# IWRL6432AOP.net
KiCad netlist of a schematic drawn in Altium Designer
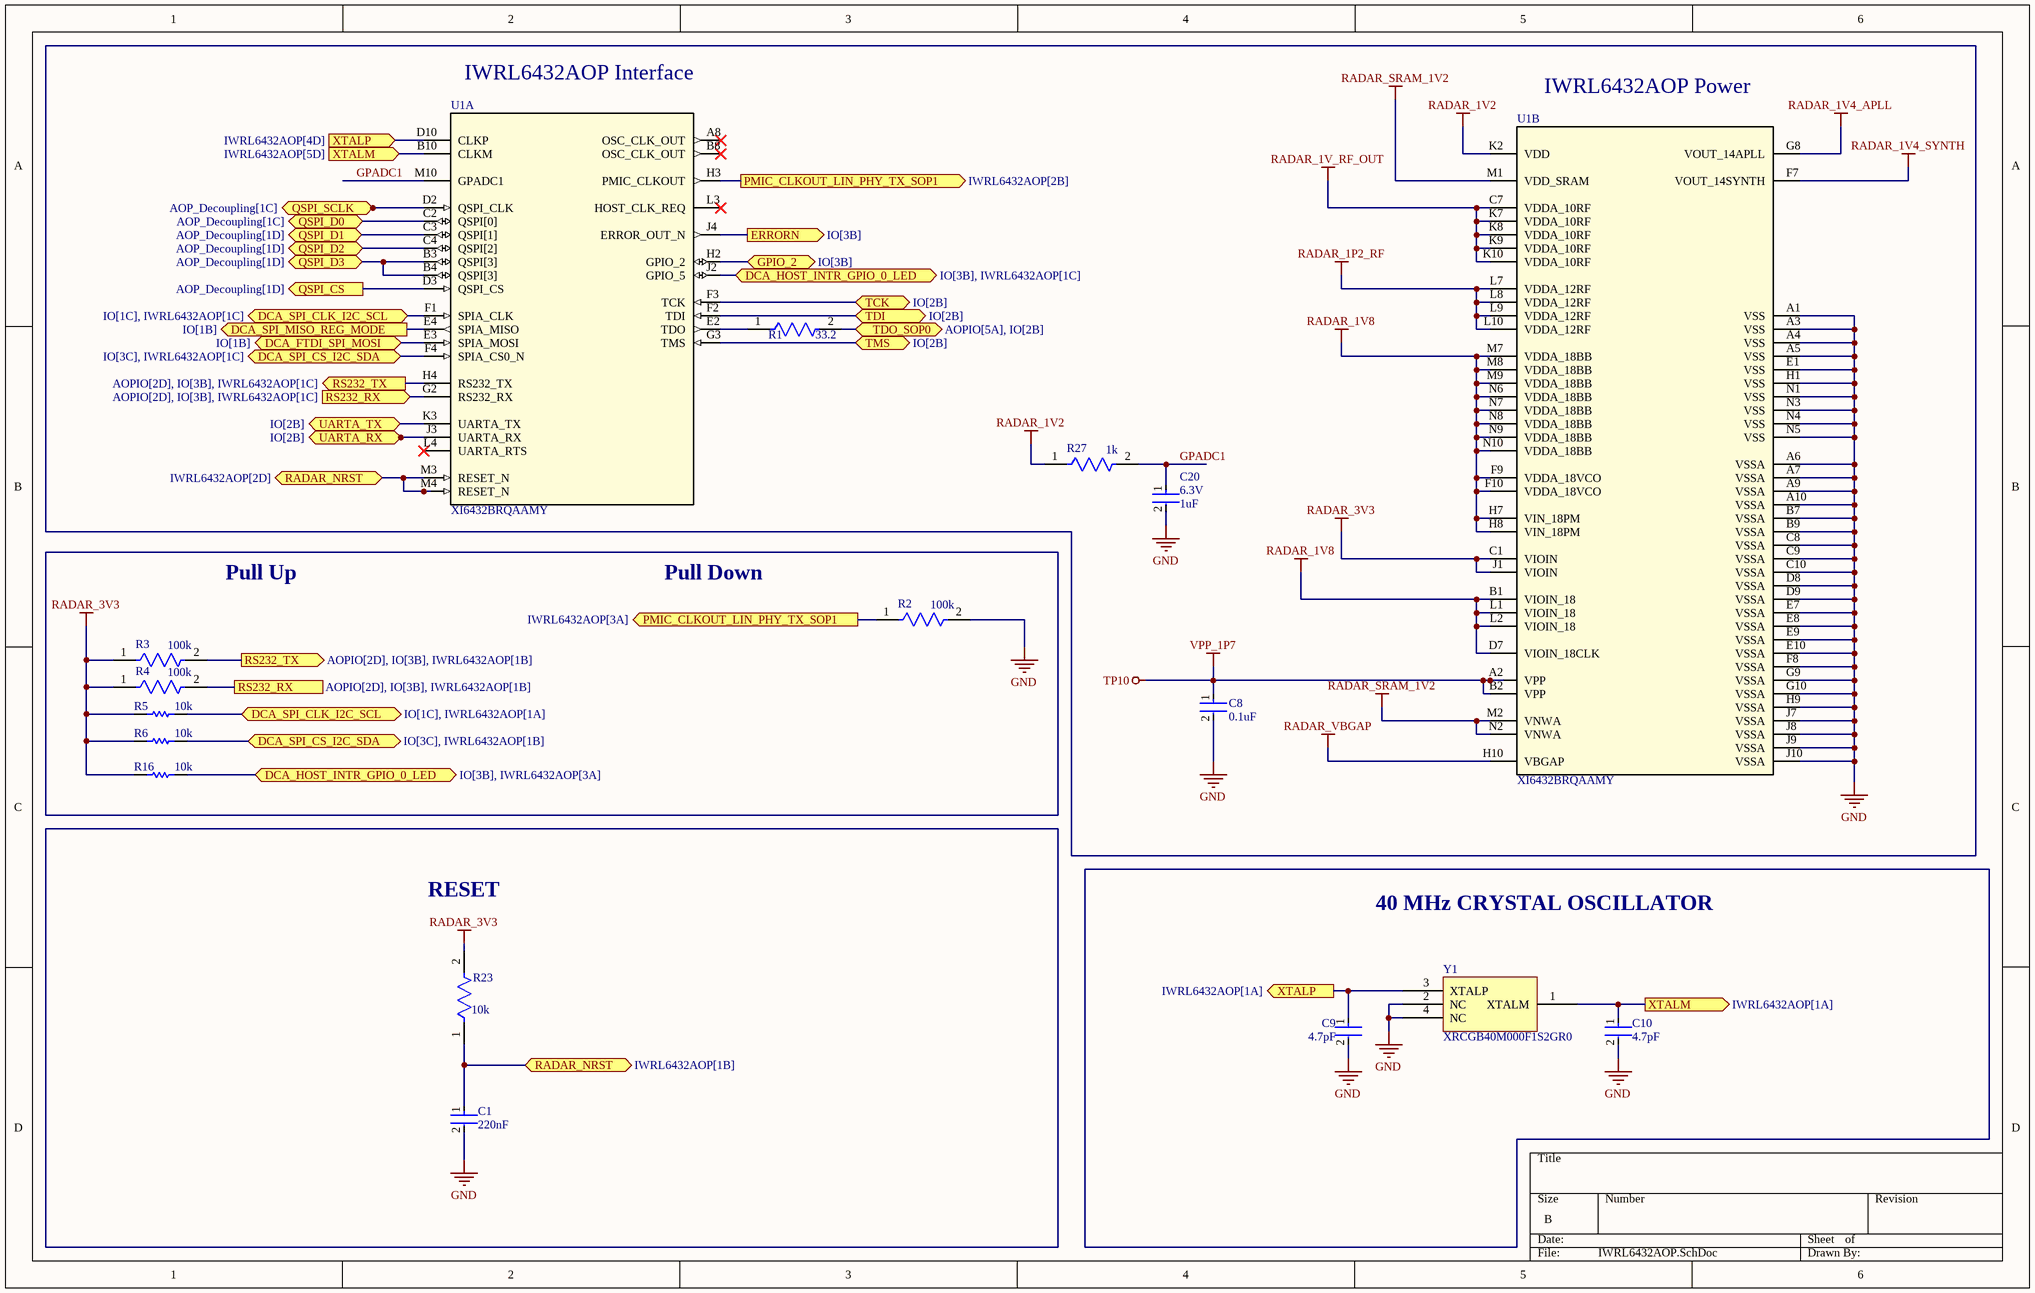
[diagram p0: IWRL6432AOP.SchDoc]

(export (version "E")
  (design (tool "Eeschema 10.0.6"))
  (components
    (comp (ref "C1")
      (value "CL05B224KO5NNNC")
      (footprint "FP-CL549-IPC_C")
      (description "Cap Ceramic 220nF 16V X7R ±10% SMD 0402 +125°C Paper T/R")
      (fields (field (name "CAPACITANCE") "220nF") (field (name "TOLERANCE") "10%"))
      (libsource (lib "Altium Content Vault") (part "b4654b650e69147ec39a6b967a45e02"))
    )
    (comp (ref "C8")
      (value "0.1uF")
      (footprint "FP-C0402-BB-MFG")
      (description "CAP CER 0.1UF 10V X7R 0402")
      (fields
        (field (name "OCTOPART") "https://octopart.com/c0402c104k8ractu-kemet-106349")
        (field (name "MANUFACTURER PART NUMBER") "C0402C104K8RACTU")
      )
      (libsource (lib "Altium Content Vault") (part "b4654b650e69147ec39a6b967a45e02"))
    )
    (comp (ref "C9")
      (value "GJM1555C1H4R7BB01D")
      (footprint "FP-GJM155-0_05-IPC_C")
      (description "Multi-Layer Ceramic Capacitor 4.7pF C0G  ±0.1pF 0402 Paper T/R")
      (fields (field (name "CAPACITANCE") "4.7pF"))
      (libsource (lib "Altium Content Vault") (part "02cd4be3c70576c341d710602a673aa"))
    )
    (comp (ref "C10")
      (value "GJM1555C1H4R7BB01D")
      (footprint "FP-GJM155-0_05-IPC_C")
      (description "Multi-Layer Ceramic Capacitor 4.7pF C0G  ±0.1pF 0402 Paper T/R")
      (fields (field (name "CAPACITANCE") "4.7pF"))
      (libsource (lib "Altium Content Vault") (part "02cd4be3c70576c341d710602a673aa"))
    )
    (comp (ref "C20")
      (value "GRM155C80J105KA12D")
      (footprint "FP-GRM155-0_05-IPC_C")
      (description "Chip Multilayer Ceramic Capacitors for General Purpose, 0402, 1.0uF, X6S, 22%, 10%, 6.3V")
      (fields
        (field (name "CAPACITANCE") "1uF")
        (field (name "TOLERANCE") "10%")
        (field (name "VOLTAGE RATING (DC)") "6.3V")
      )
      (libsource (lib "Altium Content Vault") (part "02cd4be3c70576c341d710602a673aa"))
    )
    (comp (ref "R1")
      (value "RT0402FRE0733R2L")
      (footprint "FP-RT0402-0_35-MFG")
      (fields (field (name "TOLERANCE") "1%") (field (name "RESISTANCE") "33.2"))
      (libsource (lib "Altium Content Vault") (part "1029c3af85768c4190bb7ad29bc67b5"))
    )
    (comp (ref "R2")
      (value "CRCW0402100KFKEDC")
      (footprint "FP-CRCW0402-C-e3-MFG")
      (description "RES 100K OHM 1% 1/16W 0402")
      (fields (field (name "TOLERANCE") "1%") (field (name "RESISTANCE") "100k"))
      (libsource (lib "Altium Content Vault") (part "1029c3af85768c4190bb7ad29bc67b5"))
    )
    (comp (ref "R3")
      (value "CRCW0402100KFKEDC")
      (footprint "FP-CRCW0402-C-e3-MFG")
      (description "RES 100K OHM 1% 1/16W 0402")
      (fields (field (name "TOLERANCE") "1%") (field (name "RESISTANCE") "100k"))
      (libsource (lib "Altium Content Vault") (part "1029c3af85768c4190bb7ad29bc67b5"))
    )
    (comp (ref "R4")
      (value "CRCW0402100KFKEDC")
      (footprint "FP-CRCW0402-C-e3-MFG")
      (description "RES 100K OHM 1% 1/16W 0402")
      (fields (field (name "TOLERANCE") "1%") (field (name "RESISTANCE") "100k"))
      (libsource (lib "Altium Content Vault") (part "1029c3af85768c4190bb7ad29bc67b5"))
    )
    (comp (ref "R5")
      (value "10k")
      (footprint "RESC1005X40X25LL05T10")
      (fields (field (name "PART NUMBER") "RC0402FR-0710KL") (field (name "MANUFACTURER") "Yageo / Phycomp"))
      (libsource (lib "Altium Content Vault") (part "RES"))
    )
    (comp (ref "R6")
      (value "10k")
      (footprint "RESC1005X40X25LL05T10")
      (fields (field (name "PART NUMBER") "RC0402FR-0710KL") (field (name "MANUFACTURER") "Yageo / Phycomp"))
      (libsource (lib "Altium Content Vault") (part "RES"))
    )
    (comp (ref "R16")
      (value "10k")
      (footprint "RESC1005X40X25LL05T10")
      (fields (field (name "PART NUMBER") "RC0402FR-0710KL") (field (name "MANUFACTURER") "Yageo / Phycomp"))
      (libsource (lib "Altium Content Vault") (part "RES"))
    )
    (comp (ref "R23")
      (value "ERJ-1RHD1002C")
      (footprint "FP-ERJ1R-MFG")
      (description "RES SMD 10K OHM 0.5% 1/20W 0201")
      (fields (field (name "TOLERANCE") "0.5%") (field (name "RESISTANCE") "10k"))
      (libsource (lib "Altium Content Vault") (part "1029c3af85768c4190bb7ad29bc67b5"))
    )
    (comp (ref "R27")
      (value "RC0402FR-071KL")
      (footprint "FP-RC0402-0_4-IPC_A")
      (description "RES 1K OHM 1% 1/16W 0402")
      (fields (field (name "TOLERANCE") "1%") (field (name "RESISTANCE") "1k"))
      (libsource (lib "Altium Content Vault") (part "1029c3af85768c4190bb7ad29bc67b5"))
    )
    (comp (ref "U1")
      (value "XI6432BRQAAMY")
      (footprint "AMY0101A-MFG")
      (fields (field (name "COPYRIGHT") "Copyright (C) 2026 Ultra Librarian. All rights reserved."))
      (libsource (lib "XI6432BRQAAMY") (part "XI6432BRQAAMY"))
    )
    (comp (ref "Y1")
      (value "XRCGB40M000F1S2GR0")
      (footprint "XRCGB40M000F1S2GR0")
      (description "Crystal, 40MHZ, 8PF, SMD, 2MM X 1.6MM;")
      (fields (field (name "MANUFACTURER") "Murata"))
      (libsource (lib "Schlib1") (part "XRCGB40M000F1S2GR0"))
    )
  )
  (nets
    (net (code "1") (name "/DCA_FTDI_SPI_MOSI") (class "Default")
      (node (ref "U1") (pin "E3") (pinfunction "SPIA_MOSI_E3") (pintype "input"))
    )
    (net (code "2") (name "/DCA_HOST_INTR_GPIO_0_LED") (class "Default")
      (node (ref "R16") (pin "2") (pinfunction "2_2") (pintype "passive"))
      (node (ref "U1") (pin "J2") (pinfunction "GPIO_5_J2") (pintype "bidirectional"))
    )
    (net (code "3") (name "/DCA_SPI_CLK_I2C_SCL") (class "Default")
      (node (ref "R5") (pin "2") (pinfunction "2_2") (pintype "passive"))
      (node (ref "U1") (pin "F1") (pinfunction "SPIA_CLK_F1") (pintype "input"))
    )
    (net (code "4") (name "/DCA_SPI_CS_I2C_SDA") (class "Default")
      (node (ref "R6") (pin "2") (pinfunction "2_2") (pintype "passive"))
      (node (ref "U1") (pin "F4") (pinfunction "SPIA_CS0_N_F4") (pintype "input"))
    )
    (net (code "5") (name "/DCA_SPI_MISO_REG_MODE") (class "Default")
      (node (ref "U1") (pin "E4") (pinfunction "SPIA_MISO_E4") (pintype "output"))
    )
    (net (code "6") (name "/ERRORN") (class "Default")
      (node (ref "U1") (pin "J4") (pinfunction "ERROR_OUT_N_J4") (pintype "output"))
    )
    (net (code "7") (name "/GPADC1") (class "Default")
      (node (ref "C20") (pin "1") (pinfunction "1_1") (pintype "passive"))
      (node (ref "R27") (pin "2") (pinfunction "2_2") (pintype "passive"))
      (node (ref "U1") (pin "M10") (pinfunction "GPADC1_M10") (pintype "passive"))
    )
    (net (code "8") (name "/GPIO_2") (class "Default")
      (node (ref "U1") (pin "H2") (pinfunction "GPIO_2_H2") (pintype "bidirectional"))
    )
    (net (code "9") (name "/PMIC_CLKOUT_LIN_PHY_TX_SOP1") (class "Default")
      (node (ref "R2") (pin "1") (pinfunction "1_1") (pintype "passive"))
      (node (ref "U1") (pin "H3") (pinfunction "PMIC_CLKOUT_H3") (pintype "output"))
    )
    (net (code "10") (name "/QSPI_CS") (class "Default")
      (node (ref "U1") (pin "D3") (pinfunction "QSPI_CS_D3") (pintype "input"))
    )
    (net (code "11") (name "/QSPI_D0") (class "Default")
      (node (ref "U1") (pin "C2") (pinfunction "QSPI[0]_C2") (pintype "bidirectional"))
    )
    (net (code "12") (name "/QSPI_D1") (class "Default")
      (node (ref "U1") (pin "C3") (pinfunction "QSPI[1]_C3") (pintype "bidirectional"))
    )
    (net (code "13") (name "/QSPI_D2") (class "Default")
      (node (ref "U1") (pin "C4") (pinfunction "QSPI[2]_C4") (pintype "bidirectional"))
    )
    (net (code "14") (name "/QSPI_D3") (class "Default")
      (node (ref "U1") (pin "B3") (pinfunction "QSPI[3]_B3") (pintype "bidirectional"))
      (node (ref "U1") (pin "B4") (pinfunction "QSPI[3]_B4") (pintype "bidirectional"))
    )
    (net (code "15") (name "/QSPI_SCLK") (class "Default")
      (node (ref "U1") (pin "D2") (pinfunction "QSPI_CLK_D2") (pintype "input"))
    )
    (net (code "16") (name "/RADAR_NRST") (class "Default")
      (node (ref "C1") (pin "1") (pinfunction "1_1") (pintype "passive"))
      (node (ref "R23") (pin "1") (pinfunction "1_1") (pintype "passive"))
      (node (ref "U1") (pin "M3") (pinfunction "RESET_N_M3") (pintype "input"))
      (node (ref "U1") (pin "M4") (pinfunction "RESET_N_M4") (pintype "input"))
    )
    (net (code "17") (name "/RS232_RX") (class "Default")
      (node (ref "R4") (pin "2") (pinfunction "2_2") (pintype "passive"))
      (node (ref "U1") (pin "G2") (pinfunction "RS232_RX_G2") (pintype "passive"))
    )
    (net (code "18") (name "/RS232_TX") (class "Default")
      (node (ref "R3") (pin "2") (pinfunction "2_2") (pintype "passive"))
      (node (ref "U1") (pin "H4") (pinfunction "RS232_TX_H4") (pintype "passive"))
    )
    (net (code "19") (name "/TCK") (class "Default")
      (node (ref "U1") (pin "F3") (pinfunction "TCK_F3") (pintype "input"))
    )
    (net (code "20") (name "/TDI") (class "Default")
      (node (ref "U1") (pin "F2") (pinfunction "TDI_F2") (pintype "input"))
    )
    (net (code "21") (name "/TDO_SOP0") (class "Default")
      (node (ref "R1") (pin "2") (pinfunction "2_2") (pintype "passive"))
    )
    (net (code "22") (name "/TMS") (class "Default")
      (node (ref "U1") (pin "G3") (pinfunction "TMS_G3") (pintype "input"))
    )
    (net (code "23") (name "/UARTA_RX") (class "Default")
      (node (ref "U1") (pin "J3") (pinfunction "UARTA_RX_J3") (pintype "passive"))
    )
    (net (code "24") (name "/UARTA_TX") (class "Default")
      (node (ref "U1") (pin "K3") (pinfunction "UARTA_TX_K3") (pintype "passive"))
    )
    (net (code "25") (name "/XTALM") (class "Default")
      (node (ref "C10") (pin "1") (pinfunction "1_1") (pintype "passive"))
      (node (ref "U1") (pin "B10") (pinfunction "CLKM_B10") (pintype "passive"))
      (node (ref "Y1") (pin "1") (pinfunction "XTALM_1") (pintype "passive"))
    )
    (net (code "26") (name "/XTALP") (class "Default")
      (node (ref "C9") (pin "1") (pinfunction "1_1") (pintype "passive"))
      (node (ref "U1") (pin "D10") (pinfunction "CLKP_D10") (pintype "passive"))
      (node (ref "Y1") (pin "3") (pinfunction "XTALP_3") (pintype "passive"))
    )
    (net (code "27") (name "GND") (class "Default")
      (node (ref "C1") (pin "2") (pinfunction "2_2") (pintype "passive"))
      (node (ref "C10") (pin "2") (pinfunction "2_2") (pintype "passive"))
      (node (ref "C20") (pin "2") (pinfunction "2_2") (pintype "passive"))
      (node (ref "C8") (pin "2") (pinfunction "2_2") (pintype "passive"))
      (node (ref "C9") (pin "2") (pinfunction "2_2") (pintype "passive"))
      (node (ref "R2") (pin "2") (pinfunction "2_2") (pintype "passive"))
      (node (ref "U1") (pin "A1") (pinfunction "VSS_A1") (pintype "power_in"))
      (node (ref "U1") (pin "A10") (pinfunction "VSSA_A10") (pintype "power_in"))
      (node (ref "U1") (pin "A3") (pinfunction "VSS_A3") (pintype "power_in"))
      (node (ref "U1") (pin "A4") (pinfunction "VSS_A4") (pintype "power_in"))
      (node (ref "U1") (pin "A5") (pinfunction "VSS_A5") (pintype "power_in"))
      (node (ref "U1") (pin "A6") (pinfunction "VSSA_A6") (pintype "power_in"))
      (node (ref "U1") (pin "A7") (pinfunction "VSSA_A7") (pintype "power_in"))
      (node (ref "U1") (pin "A9") (pinfunction "VSSA_A9") (pintype "power_in"))
      (node (ref "U1") (pin "B7") (pinfunction "VSSA_B7") (pintype "power_in"))
      (node (ref "U1") (pin "B9") (pinfunction "VSSA_B9") (pintype "power_in"))
      (node (ref "U1") (pin "C10") (pinfunction "VSSA_C10") (pintype "power_in"))
      (node (ref "U1") (pin "C8") (pinfunction "VSSA_C8") (pintype "power_in"))
      (node (ref "U1") (pin "C9") (pinfunction "VSSA_C9") (pintype "power_in"))
      (node (ref "U1") (pin "D8") (pinfunction "VSSA_D8") (pintype "power_in"))
      (node (ref "U1") (pin "D9") (pinfunction "VSSA_D9") (pintype "power_in"))
      (node (ref "U1") (pin "E1") (pinfunction "VSS_E1") (pintype "power_in"))
      (node (ref "U1") (pin "E10") (pinfunction "VSSA_E10") (pintype "power_in"))
      (node (ref "U1") (pin "E7") (pinfunction "VSSA_E7") (pintype "power_in"))
      (node (ref "U1") (pin "E8") (pinfunction "VSSA_E8") (pintype "power_in"))
      (node (ref "U1") (pin "E9") (pinfunction "VSSA_E9") (pintype "power_in"))
      (node (ref "U1") (pin "F8") (pinfunction "VSSA_F8") (pintype "power_in"))
      (node (ref "U1") (pin "G10") (pinfunction "VSSA_G10") (pintype "power_in"))
      (node (ref "U1") (pin "G9") (pinfunction "VSSA_G9") (pintype "power_in"))
      (node (ref "U1") (pin "H1") (pinfunction "VSS_H1") (pintype "power_in"))
      (node (ref "U1") (pin "H9") (pinfunction "VSSA_H9") (pintype "power_in"))
      (node (ref "U1") (pin "J10") (pinfunction "VSSA_J10") (pintype "power_in"))
      (node (ref "U1") (pin "J7") (pinfunction "VSSA_J7") (pintype "power_in"))
      (node (ref "U1") (pin "J8") (pinfunction "VSSA_J8") (pintype "power_in"))
      (node (ref "U1") (pin "J9") (pinfunction "VSSA_J9") (pintype "power_in"))
      (node (ref "U1") (pin "N1") (pinfunction "VSS_N1") (pintype "power_in"))
      (node (ref "U1") (pin "N3") (pinfunction "VSS_N3") (pintype "power_in"))
      (node (ref "U1") (pin "N4") (pinfunction "VSS_N4") (pintype "power_in"))
      (node (ref "U1") (pin "N5") (pinfunction "VSS_N5") (pintype "power_in"))
      (node (ref "Y1") (pin "2") (pinfunction "NC_2") (pintype "passive"))
      (node (ref "Y1") (pin "4") (pinfunction "NC_4") (pintype "passive"))
    )
    (net (code "28") (name "Net-(U1A-TDO)") (class "Default")
      (node (ref "R1") (pin "1") (pinfunction "1_1") (pintype "passive"))
      (node (ref "U1") (pin "E2") (pinfunction "TDO_E2") (pintype "output"))
    )
    (net (code "29") (name "RADAR_1P2_RF") (class "Default")
      (node (ref "U1") (pin "L10") (pinfunction "VDDA_12RF_L10") (pintype "power_in"))
      (node (ref "U1") (pin "L7") (pinfunction "VDDA_12RF_L7") (pintype "power_in"))
      (node (ref "U1") (pin "L8") (pinfunction "VDDA_12RF_L8") (pintype "power_in"))
      (node (ref "U1") (pin "L9") (pinfunction "VDDA_12RF_L9") (pintype "power_in"))
    )
    (net (code "30") (name "RADAR_1V2") (class "Default")
      (node (ref "R27") (pin "1") (pinfunction "1_1") (pintype "passive"))
      (node (ref "U1") (pin "K2") (pinfunction "VDD_K2") (pintype "power_in"))
    )
    (net (code "31") (name "RADAR_1V4_APLL") (class "Default")
      (node (ref "U1") (pin "G8") (pinfunction "VOUT_14APLL_G8") (pintype "power_in"))
    )
    (net (code "32") (name "RADAR_1V4_SYNTH") (class "Default")
      (node (ref "U1") (pin "F7") (pinfunction "VOUT_14SYNTH_F7") (pintype "power_in"))
    )
    (net (code "33") (name "RADAR_1V8") (class "Default")
      (node (ref "U1") (pin "B1") (pinfunction "VIOIN_18_B1") (pintype "power_in"))
      (node (ref "U1") (pin "D7") (pinfunction "VIOIN_18CLK_D7") (pintype "power_in"))
      (node (ref "U1") (pin "F10") (pinfunction "VDDA_18VCO_F10") (pintype "power_in"))
      (node (ref "U1") (pin "F9") (pinfunction "VDDA_18VCO_F9") (pintype "power_in"))
      (node (ref "U1") (pin "H7") (pinfunction "VIN_18PM_H7") (pintype "power_in"))
      (node (ref "U1") (pin "H8") (pinfunction "VIN_18PM_H8") (pintype "power_in"))
      (node (ref "U1") (pin "L1") (pinfunction "VIOIN_18_L1") (pintype "power_in"))
      (node (ref "U1") (pin "L2") (pinfunction "VIOIN_18_L2") (pintype "power_in"))
      (node (ref "U1") (pin "M7") (pinfunction "VDDA_18BB_M7") (pintype "power_in"))
      (node (ref "U1") (pin "M8") (pinfunction "VDDA_18BB_M8") (pintype "power_in"))
      (node (ref "U1") (pin "M9") (pinfunction "VDDA_18BB_M9") (pintype "power_in"))
      (node (ref "U1") (pin "N10") (pinfunction "VDDA_18BB_N10") (pintype "power_in"))
      (node (ref "U1") (pin "N6") (pinfunction "VDDA_18BB_N6") (pintype "power_in"))
      (node (ref "U1") (pin "N7") (pinfunction "VDDA_18BB_N7") (pintype "power_in"))
      (node (ref "U1") (pin "N8") (pinfunction "VDDA_18BB_N8") (pintype "power_in"))
      (node (ref "U1") (pin "N9") (pinfunction "VDDA_18BB_N9") (pintype "power_in"))
    )
    (net (code "34") (name "RADAR_1V_RF_OUT") (class "Default")
      (node (ref "U1") (pin "C7") (pinfunction "VDDA_10RF_C7") (pintype "power_in"))
      (node (ref "U1") (pin "K10") (pinfunction "VDDA_10RF_K10") (pintype "power_in"))
      (node (ref "U1") (pin "K7") (pinfunction "VDDA_10RF_K7") (pintype "power_in"))
      (node (ref "U1") (pin "K8") (pinfunction "VDDA_10RF_K8") (pintype "power_in"))
      (node (ref "U1") (pin "K9") (pinfunction "VDDA_10RF_K9") (pintype "power_in"))
    )
    (net (code "35") (name "RADAR_3V3") (class "Default")
      (node (ref "R16") (pin "1") (pinfunction "1_1") (pintype "passive"))
      (node (ref "R23") (pin "2") (pinfunction "2_2") (pintype "passive"))
      (node (ref "R3") (pin "1") (pinfunction "1_1") (pintype "passive"))
      (node (ref "R4") (pin "1") (pinfunction "1_1") (pintype "passive"))
      (node (ref "R5") (pin "1") (pinfunction "1_1") (pintype "passive"))
      (node (ref "R6") (pin "1") (pinfunction "1_1") (pintype "passive"))
      (node (ref "U1") (pin "C1") (pinfunction "VIOIN_C1") (pintype "power_in"))
      (node (ref "U1") (pin "J1") (pinfunction "VIOIN_J1") (pintype "power_in"))
    )
    (net (code "36") (name "RADAR_SRAM_1V2") (class "Default")
      (node (ref "U1") (pin "M1") (pinfunction "VDD_SRAM_M1") (pintype "power_in"))
      (node (ref "U1") (pin "M2") (pinfunction "VNWA_M2") (pintype "power_in"))
      (node (ref "U1") (pin "N2") (pinfunction "VNWA_N2") (pintype "power_in"))
    )
    (net (code "37") (name "RADAR_VBGAP") (class "Default")
      (node (ref "U1") (pin "H10") (pinfunction "VBGAP_H10") (pintype "power_in"))
    )
    (net (code "38") (name "TP10") (class "Default")
      (node (ref "C8") (pin "1") (pinfunction "1_1") (pintype "passive"))
      (node (ref "U1") (pin "A2") (pinfunction "VPP_A2") (pintype "power_in"))
      (node (ref "U1") (pin "B2") (pinfunction "VPP_B2") (pintype "power_in"))
    )
    (net (code "39") (name "unconnected-(U1A-HOST_CLK_REQ-PadL3)") (class "Default")
      (node (ref "U1") (pin "L3") (pinfunction "HOST_CLK_REQ_L3") (pintype "passive+no_connect"))
    )
    (net (code "40") (name "unconnected-(U1A-OSC_CLK_OUT-PadA8)") (class "Default")
      (node (ref "U1") (pin "A8") (pinfunction "OSC_CLK_OUT_A8") (pintype "output+no_connect"))
    )
    (net (code "41") (name "unconnected-(U1A-OSC_CLK_OUT-PadB8)") (class "Default")
      (node (ref "U1") (pin "B8") (pinfunction "OSC_CLK_OUT_B8") (pintype "output+no_connect"))
    )
    (net (code "42") (name "unconnected-(U1A-UARTA_RTS-PadL4)") (class "Default")
      (node (ref "U1") (pin "L4") (pinfunction "UARTA_RTS_L4") (pintype "passive+no_connect"))
    )
  )
)
